# MPFB.net
KiCad netlist of a schematic drawn in Altium Designer
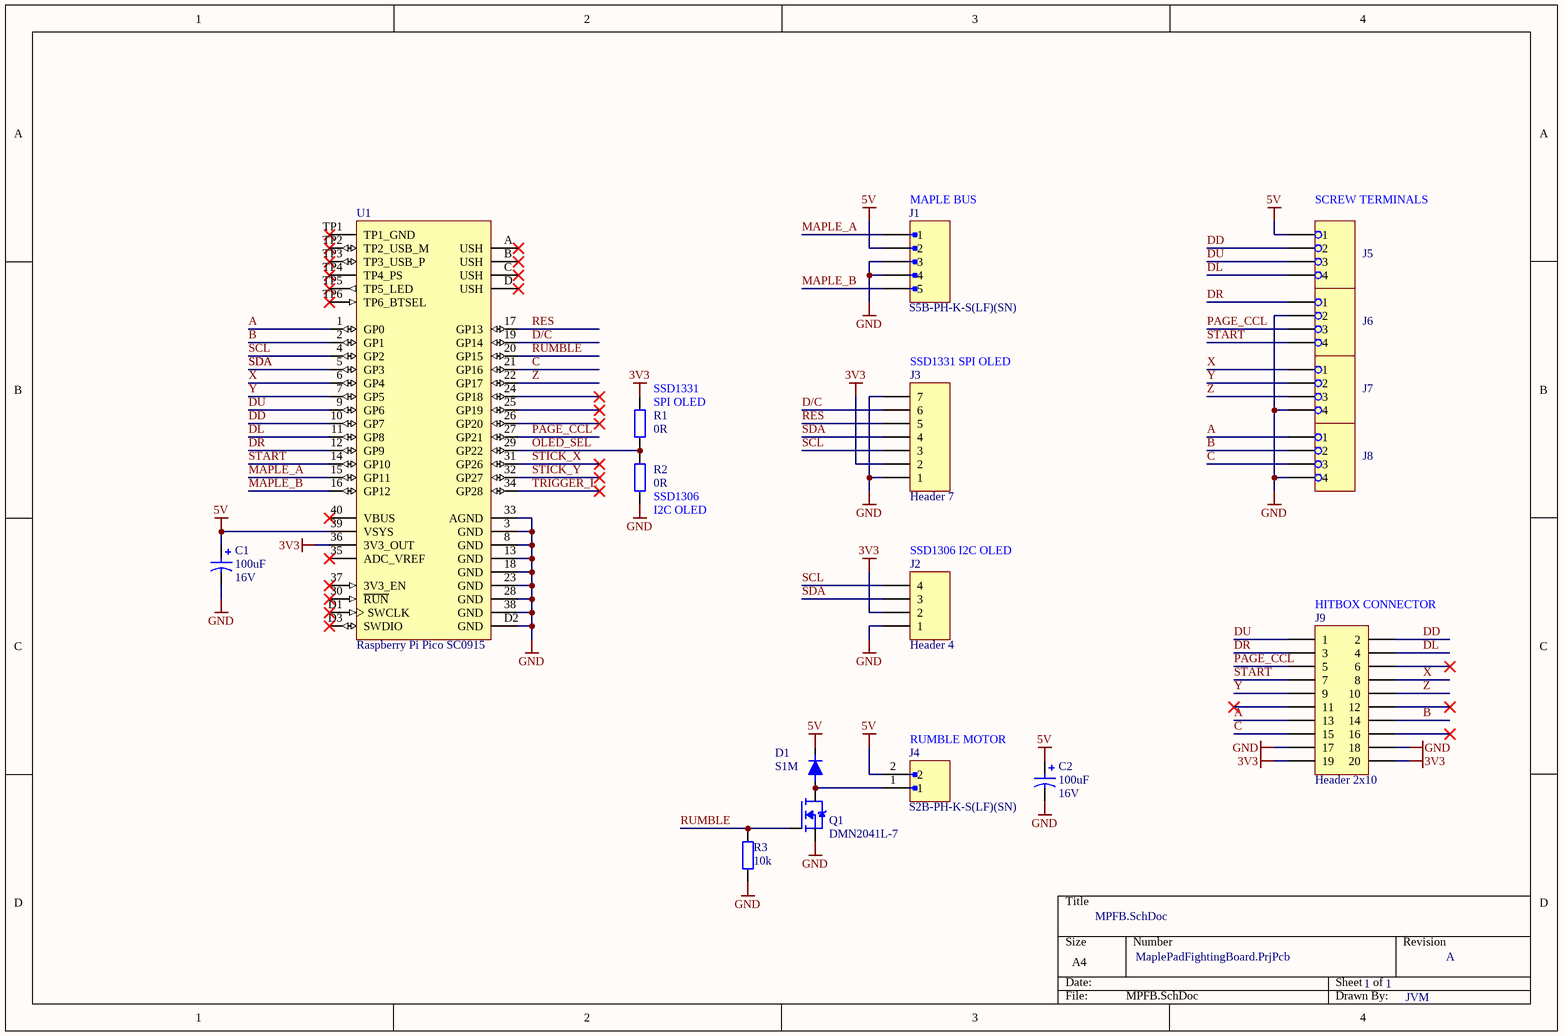
[diagram p0: MPFB.SchDoc]

(export (version "E")
  (design (tool "Eeschema 10.0.6"))
  (components
    (comp (ref "C1")
      (value "100uF")
      (footprint "Cap2.54P5.0D")
      (description "Polarized Capacitor, 2.54mm Pitch, 5mm Width")
      (fields (field (name "VOLTAGE") "16V") (field (name "Comment") "Cap2.54P5.0D"))
      (libsource (lib "MPFB_LIB") (part "Cap2.54P5.0D"))
    )
    (comp (ref "C2")
      (value "100uF")
      (footprint "Cap2.54P5.0D")
      (description "Polarized Capacitor, 2.54mm Pitch, 5mm Width")
      (fields (field (name "VOLTAGE") "16V") (field (name "Comment") "Cap2.54P5.0D"))
      (libsource (lib "MPFB_LIB") (part "Cap2.54P5.0D"))
    )
    (comp (ref "D1")
      (value "S1M")
      (footprint "DIOM5227X270N")
      (description "Diode Standard 1000 V 1A Surface Mount DO-214AC (SMA)")
      (fields (field (name "MF") "Diotec Semiconductor"))
      (libsource (lib "MPFB_LIB") (part "S1M"))
    )
    (comp (ref "J1")
      (value "S5B-PH-K-S(LF)(SN)")
      (footprint "JST_S5B-PH-K-S(LF)(SN)")
      (description "JST PH Header Through Hole, Right Angle 5 position(2.00mm)")
      (fields (field (name "MF") "JST Sales America Inc."))
      (libsource (lib "MPFB_LIB") (part "S5B-PH-K-S(LF)(SN)"))
    )
    (comp (ref "J2")
      (value "Header 4")
      (footprint "HDR1X4")
      (description "2,54mm pitch header, 4 positions")
      (libsource (lib "MPFB_LIB") (part "Header 4"))
    )
    (comp (ref "J3")
      (value "Header 7")
      (footprint "HDR1X7")
      (description "2,54mm pitch header, 7 positions")
      (libsource (lib "MPFB_LIB") (part "Header 7"))
    )
    (comp (ref "J4")
      (value "S2B-PH-K-S(LF)(SN)")
      (footprint "JST_S2B-PH-K-S(LF)(SN)")
      (description "JST PH Header Through Hole, Right Angle 2 position(2.00mm)")
      (fields (field (name "MF") "JST Sales America Inc."))
      (libsource (lib "MPFB_LIB") (part "S2B-PH-K-S(LF)(SN)"))
    )
    (comp (ref "J5")
      (value "1751264")
      (footprint "PHOENIX_1751264")
      (fields (field (name "MF") "Phoenix Contact"))
      (libsource (lib "MPFB_LIB") (part "1751264"))
    )
    (comp (ref "J6")
      (value "1751264")
      (footprint "PHOENIX_1751264")
      (fields (field (name "MF") "Phoenix Contact"))
      (libsource (lib "MPFB_LIB") (part "1751264"))
    )
    (comp (ref "J7")
      (value "1751264")
      (footprint "PHOENIX_1751264")
      (fields (field (name "MF") "Phoenix Contact"))
      (libsource (lib "MPFB_LIB") (part "1751264"))
    )
    (comp (ref "J8")
      (value "1751264")
      (footprint "PHOENIX_1751264")
      (fields (field (name "MF") "Phoenix Contact"))
      (libsource (lib "MPFB_LIB") (part "1751264"))
    )
    (comp (ref "J9")
      (value "Header 2x10")
      (footprint "HDR2X10")
      (description "2,54mm pitch header, 2x10 positions")
      (libsource (lib "MPFB_LIB") (part "Header 2x10"))
    )
    (comp (ref "Q1")
      (value "DMN2041L-7")
      (footprint "SOT91P240X110-3N")
      (description "MOSFET N-Channel 20V 6.4A SOT23 ¦ Diodes Inc DMN2041L-7")
      (fields (field (name "MF") "Diodes Inc."))
      (libsource (lib "MPFB_LIB") (part "DMN2041L-7"))
    )
    (comp (ref "R1")
      (value "0R")
      (footprint "RESC1608N")
      (description "Resistor (SMD), 0603")
      (fields (field (name "Comment") "Res0603"))
      (libsource (lib "MPFB_LIB") (part "Res0603"))
    )
    (comp (ref "R2")
      (value "0R")
      (footprint "RESC1608N")
      (description "Resistor (SMD), 0603")
      (fields (field (name "Comment") "Res0603"))
      (libsource (lib "MPFB_LIB") (part "Res0603"))
    )
    (comp (ref "R3")
      (value "10k")
      (footprint "RESC2012N")
      (description "Resistor (SMD), 0805")
      (fields (field (name "Comment") "Res0805"))
      (libsource (lib "MPFB_LIB") (part "Res0805"))
    )
    (comp (ref "U1")
      (value "Raspberry Pi Pico SC0915")
      (footprint "MODULE_SC0915")
      (description "Raspberry Pi Pico")
      (fields (field (name "MP") "SC0915") (field (name "MF") "Raspberry Pi"))
      (libsource (lib "MPFB_LIB") (part "SC0915"))
    )
  )
  (nets
    (net (code "1") (name "/A") (class "Default")
      (node (ref "J8") (pin "1") (pinfunction "1_1") (pintype "passive"))
      (node (ref "J9") (pin "13") (pinfunction "13_13") (pintype "passive"))
      (node (ref "U1") (pin "1") (pinfunction "GP0_1") (pintype "bidirectional"))
    )
    (net (code "2") (name "/B") (class "Default")
      (node (ref "J8") (pin "2") (pinfunction "2_2") (pintype "passive"))
      (node (ref "J9") (pin "14") (pinfunction "14_14") (pintype "passive"))
      (node (ref "U1") (pin "2") (pinfunction "GP1_2") (pintype "bidirectional"))
    )
    (net (code "3") (name "/C") (class "Default")
      (node (ref "J8") (pin "3") (pinfunction "3_3") (pintype "passive"))
      (node (ref "J9") (pin "15") (pinfunction "15_15") (pintype "passive"))
      (node (ref "U1") (pin "21") (pinfunction "GP16_21") (pintype "bidirectional"))
    )
    (net (code "4") (name "/DD") (class "Default")
      (node (ref "J5") (pin "2") (pinfunction "2_2") (pintype "passive"))
      (node (ref "J9") (pin "2") (pinfunction "2_2") (pintype "passive"))
      (node (ref "U1") (pin "10") (pinfunction "GP7_10") (pintype "bidirectional"))
    )
    (net (code "5") (name "/DL") (class "Default")
      (node (ref "J5") (pin "4") (pinfunction "4_4") (pintype "passive"))
      (node (ref "J9") (pin "4") (pinfunction "4_4") (pintype "passive"))
      (node (ref "U1") (pin "11") (pinfunction "GP8_11") (pintype "bidirectional"))
    )
    (net (code "6") (name "/DR") (class "Default")
      (node (ref "J6") (pin "1") (pinfunction "1_1") (pintype "passive"))
      (node (ref "J9") (pin "3") (pinfunction "3_3") (pintype "passive"))
      (node (ref "U1") (pin "12") (pinfunction "GP9_12") (pintype "bidirectional"))
    )
    (net (code "7") (name "/DU") (class "Default")
      (node (ref "J5") (pin "3") (pinfunction "3_3") (pintype "passive"))
      (node (ref "J9") (pin "1") (pinfunction "1_1") (pintype "passive"))
      (node (ref "U1") (pin "9") (pinfunction "GP6_9") (pintype "bidirectional"))
    )
    (net (code "8") (name "/D{slash}C") (class "Default")
      (node (ref "J3") (pin "6") (pinfunction "6_6") (pintype "passive"))
      (node (ref "U1") (pin "19") (pinfunction "GP14_19") (pintype "bidirectional"))
    )
    (net (code "9") (name "/MAPLE_A") (class "Default")
      (node (ref "J1") (pin "1") (pinfunction "1_1") (pintype "passive"))
      (node (ref "U1") (pin "15") (pinfunction "GP11_15") (pintype "bidirectional"))
    )
    (net (code "10") (name "/MAPLE_B") (class "Default")
      (node (ref "J1") (pin "5") (pinfunction "5_5") (pintype "passive"))
      (node (ref "U1") (pin "16") (pinfunction "GP12_16") (pintype "bidirectional"))
    )
    (net (code "11") (name "/OLED_SEL") (class "Default")
      (node (ref "R1") (pin "1") (pinfunction "1_1") (pintype "passive"))
      (node (ref "R2") (pin "2") (pinfunction "2_2") (pintype "passive"))
      (node (ref "U1") (pin "29") (pinfunction "GP22_29") (pintype "bidirectional"))
    )
    (net (code "12") (name "/PAGE_CCL") (class "Default")
      (node (ref "J6") (pin "3") (pinfunction "3_3") (pintype "passive"))
      (node (ref "J9") (pin "5") (pinfunction "5_5") (pintype "passive"))
      (node (ref "U1") (pin "27") (pinfunction "GP21_27") (pintype "bidirectional"))
    )
    (net (code "13") (name "/RES") (class "Default")
      (node (ref "J3") (pin "5") (pinfunction "5_5") (pintype "passive"))
      (node (ref "U1") (pin "17") (pinfunction "GP13_17") (pintype "bidirectional"))
    )
    (net (code "14") (name "/RUMBLE") (class "Default")
      (node (ref "Q1") (pin "1") (pinfunction "G_1") (pintype "passive"))
      (node (ref "R3") (pin "2") (pinfunction "2_2") (pintype "passive"))
      (node (ref "U1") (pin "20") (pinfunction "GP15_20") (pintype "bidirectional"))
    )
    (net (code "15") (name "/SCL") (class "Default")
      (node (ref "J2") (pin "4") (pinfunction "4_4") (pintype "passive"))
      (node (ref "J3") (pin "3") (pinfunction "3_3") (pintype "passive"))
      (node (ref "U1") (pin "4") (pinfunction "GP2_4") (pintype "bidirectional"))
    )
    (net (code "16") (name "/SDA") (class "Default")
      (node (ref "J2") (pin "3") (pinfunction "3_3") (pintype "passive"))
      (node (ref "J3") (pin "4") (pinfunction "4_4") (pintype "passive"))
      (node (ref "U1") (pin "5") (pinfunction "GP3_5") (pintype "bidirectional"))
    )
    (net (code "17") (name "/START") (class "Default")
      (node (ref "J6") (pin "4") (pinfunction "4_4") (pintype "passive"))
      (node (ref "J9") (pin "7") (pinfunction "7_7") (pintype "passive"))
      (node (ref "U1") (pin "14") (pinfunction "GP10_14") (pintype "bidirectional"))
    )
    (net (code "18") (name "/STICK_X") (class "Default")
      (node (ref "U1") (pin "31") (pinfunction "GP26_31") (pintype "bidirectional+no_connect"))
    )
    (net (code "19") (name "/STICK_Y") (class "Default")
      (node (ref "U1") (pin "32") (pinfunction "GP27_32") (pintype "bidirectional+no_connect"))
    )
    (net (code "20") (name "/TRIGGER_L") (class "Default")
      (node (ref "U1") (pin "34") (pinfunction "GP28_34") (pintype "bidirectional+no_connect"))
    )
    (net (code "21") (name "/X") (class "Default")
      (node (ref "J7") (pin "1") (pinfunction "1_1") (pintype "passive"))
      (node (ref "J9") (pin "8") (pinfunction "8_8") (pintype "passive"))
      (node (ref "U1") (pin "6") (pinfunction "GP4_6") (pintype "bidirectional"))
    )
    (net (code "22") (name "/Y") (class "Default")
      (node (ref "J7") (pin "2") (pinfunction "2_2") (pintype "passive"))
      (node (ref "J9") (pin "9") (pinfunction "9_9") (pintype "passive"))
      (node (ref "U1") (pin "7") (pinfunction "GP5_7") (pintype "bidirectional"))
    )
    (net (code "23") (name "/Z") (class "Default")
      (node (ref "J7") (pin "3") (pinfunction "3_3") (pintype "passive"))
      (node (ref "J9") (pin "10") (pinfunction "10_10") (pintype "passive"))
      (node (ref "U1") (pin "22") (pinfunction "GP17_22") (pintype "bidirectional"))
    )
    (net (code "24") (name "3V3") (class "Default")
      (node (ref "J2") (pin "2") (pinfunction "2_2") (pintype "passive"))
      (node (ref "J3") (pin "2") (pinfunction "2_2") (pintype "passive"))
      (node (ref "J9") (pin "19") (pinfunction "19_19") (pintype "passive"))
      (node (ref "J9") (pin "20") (pinfunction "20_20") (pintype "passive"))
      (node (ref "R1") (pin "2") (pinfunction "2_2") (pintype "passive"))
      (node (ref "U1") (pin "36") (pinfunction "3V3_OUT_36") (pintype "power_in"))
    )
    (net (code "25") (name "5V") (class "Default")
      (node (ref "C1") (pin "1") (pinfunction "1_1") (pintype "passive"))
      (node (ref "C2") (pin "1") (pinfunction "1_1") (pintype "passive"))
      (node (ref "D1") (pin "C") (pinfunction "K_C") (pintype "passive"))
      (node (ref "J1") (pin "2") (pinfunction "2_2") (pintype "passive"))
      (node (ref "J4") (pin "2") (pinfunction "2_2") (pintype "passive"))
      (node (ref "J5") (pin "1") (pinfunction "1_1") (pintype "passive"))
      (node (ref "U1") (pin "39") (pinfunction "VSYS_39") (pintype "power_in"))
    )
    (net (code "26") (name "GND") (class "Default")
      (node (ref "C1") (pin "2") (pinfunction "2_2") (pintype "passive"))
      (node (ref "C2") (pin "2") (pinfunction "2_2") (pintype "passive"))
      (node (ref "J1") (pin "3") (pinfunction "3_3") (pintype "passive"))
      (node (ref "J1") (pin "4") (pinfunction "4_4") (pintype "passive"))
      (node (ref "J2") (pin "1") (pinfunction "1_1") (pintype "passive"))
      (node (ref "J3") (pin "1") (pinfunction "1_1") (pintype "passive"))
      (node (ref "J3") (pin "7") (pinfunction "7_7") (pintype "passive"))
      (node (ref "J6") (pin "2") (pinfunction "2_2") (pintype "passive"))
      (node (ref "J7") (pin "4") (pinfunction "4_4") (pintype "passive"))
      (node (ref "J8") (pin "4") (pinfunction "4_4") (pintype "passive"))
      (node (ref "J9") (pin "17") (pinfunction "17_17") (pintype "passive"))
      (node (ref "J9") (pin "18") (pinfunction "18_18") (pintype "passive"))
      (node (ref "Q1") (pin "2") (pinfunction "S_2") (pintype "passive"))
      (node (ref "R2") (pin "1") (pinfunction "1_1") (pintype "passive"))
      (node (ref "R3") (pin "1") (pinfunction "1_1") (pintype "passive"))
      (node (ref "U1") (pin "13") (pinfunction "GND_13") (pintype "power_in"))
      (node (ref "U1") (pin "18") (pinfunction "GND_18") (pintype "power_in"))
      (node (ref "U1") (pin "23") (pinfunction "GND_23") (pintype "power_in"))
      (node (ref "U1") (pin "28") (pinfunction "GND_28") (pintype "power_in"))
      (node (ref "U1") (pin "3") (pinfunction "GND_3") (pintype "power_in"))
      (node (ref "U1") (pin "33") (pinfunction "AGND_33") (pintype "power_in"))
      (node (ref "U1") (pin "38") (pinfunction "GND_38") (pintype "power_in"))
      (node (ref "U1") (pin "8") (pinfunction "GND_8") (pintype "power_in"))
      (node (ref "U1") (pin "D2") (pinfunction "GND_D2") (pintype "power_in"))
    )
    (net (code "27") (name "Net-(Q1-D)") (class "Default")
      (node (ref "D1") (pin "A") (pinfunction "A_A") (pintype "passive"))
      (node (ref "J4") (pin "1") (pinfunction "1_1") (pintype "passive"))
      (node (ref "Q1") (pin "3") (pinfunction "D_3") (pintype "passive"))
    )
    (net (code "28") (name "unconnected-(J9-Pad6)") (class "Default")
      (node (ref "J9") (pin "6") (pinfunction "6_6") (pintype "passive+no_connect"))
    )
    (net (code "29") (name "unconnected-(J9-Pad11)") (class "Default")
      (node (ref "J9") (pin "11") (pinfunction "11_11") (pintype "passive+no_connect"))
    )
    (net (code "30") (name "unconnected-(J9-Pad12)") (class "Default")
      (node (ref "J9") (pin "12") (pinfunction "12_12") (pintype "passive+no_connect"))
    )
    (net (code "31") (name "unconnected-(J9-Pad16)") (class "Default")
      (node (ref "J9") (pin "16") (pinfunction "16_16") (pintype "passive+no_connect"))
    )
    (net (code "32") (name "unconnected-(U1-3V3_EN-Pad37)") (class "Default")
      (node (ref "U1") (pin "37") (pinfunction "3V3_EN_37") (pintype "input+no_connect"))
    )
    (net (code "33") (name "unconnected-(U1-ADC_VREF-Pad35)") (class "Default")
      (node (ref "U1") (pin "35") (pinfunction "ADC_VREF_35") (pintype "power_in+no_connect"))
    )
    (net (code "34") (name "unconnected-(U1-GP18-Pad24)") (class "Default")
      (node (ref "U1") (pin "24") (pinfunction "GP18_24") (pintype "bidirectional+no_connect"))
    )
    (net (code "35") (name "unconnected-(U1-GP19-Pad25)") (class "Default")
      (node (ref "U1") (pin "25") (pinfunction "GP19_25") (pintype "bidirectional+no_connect"))
    )
    (net (code "36") (name "unconnected-(U1-GP20-Pad26)") (class "Default")
      (node (ref "U1") (pin "26") (pinfunction "GP20_26") (pintype "bidirectional+no_connect"))
    )
    (net (code "37") (name "unconnected-(U1-SWCLK-PadD1)") (class "Default")
      (node (ref "U1") (pin "D1") (pinfunction "SWCLK_D1") (pintype "input+no_connect"))
    )
    (net (code "38") (name "unconnected-(U1-SWDIO-PadD3)") (class "Default")
      (node (ref "U1") (pin "D3") (pinfunction "SWDIO_D3") (pintype "bidirectional+no_connect"))
    )
    (net (code "39") (name "unconnected-(U1-TP1_GND-PadTP1)") (class "Default")
      (node (ref "U1") (pin "TP1") (pinfunction "TP1_GND_TP1") (pintype "power_in+no_connect"))
    )
    (net (code "40") (name "unconnected-(U1-TP2_USB_M-PadTP2)") (class "Default")
      (node (ref "U1") (pin "TP2") (pinfunction "TP2_USB_M_TP2") (pintype "bidirectional+no_connect"))
    )
    (net (code "41") (name "unconnected-(U1-TP3_USB_P-PadTP3)") (class "Default")
      (node (ref "U1") (pin "TP3") (pinfunction "TP3_USB_P_TP3") (pintype "bidirectional+no_connect"))
    )
    (net (code "42") (name "unconnected-(U1-TP4_PS-PadTP4)") (class "Default")
      (node (ref "U1") (pin "TP4") (pinfunction "TP4_PS_TP4") (pintype "passive+no_connect"))
    )
    (net (code "43") (name "unconnected-(U1-TP5_LED-PadTP5)") (class "Default")
      (node (ref "U1") (pin "TP5") (pinfunction "TP5_LED_TP5") (pintype "output+no_connect"))
    )
    (net (code "44") (name "unconnected-(U1-TP6_BTSEL-PadTP6)") (class "Default")
      (node (ref "U1") (pin "TP6") (pinfunction "TP6_BTSEL_TP6") (pintype "input+no_connect"))
    )
    (net (code "45") (name "unconnected-(U1-USH-PadA)") (class "Default")
      (node (ref "U1") (pin "A") (pinfunction "USH_A") (pintype "power_in+no_connect"))
    )
    (net (code "46") (name "unconnected-(U1-USH-PadB)") (class "Default")
      (node (ref "U1") (pin "B") (pinfunction "USH_B") (pintype "power_in+no_connect"))
    )
    (net (code "47") (name "unconnected-(U1-USH-PadC)") (class "Default")
      (node (ref "U1") (pin "C") (pinfunction "USH_C") (pintype "power_in+no_connect"))
    )
    (net (code "48") (name "unconnected-(U1-USH-PadD)") (class "Default")
      (node (ref "U1") (pin "D") (pinfunction "USH_D") (pintype "power_in+no_connect"))
    )
    (net (code "49") (name "unconnected-(U1-VBUS-Pad40)") (class "Default")
      (node (ref "U1") (pin "40") (pinfunction "VBUS_40") (pintype "power_in+no_connect"))
    )
    (net (code "50") (name "unconnected-(U1-~{RUN}-Pad30)") (class "Default")
      (node (ref "U1") (pin "30") (pinfunction "~{RUN}_30") (pintype "input+no_connect"))
    )
  )
)
